# OMD_105V_5V_Buck.net
KiCad netlist of a schematic drawn in Altium Designer
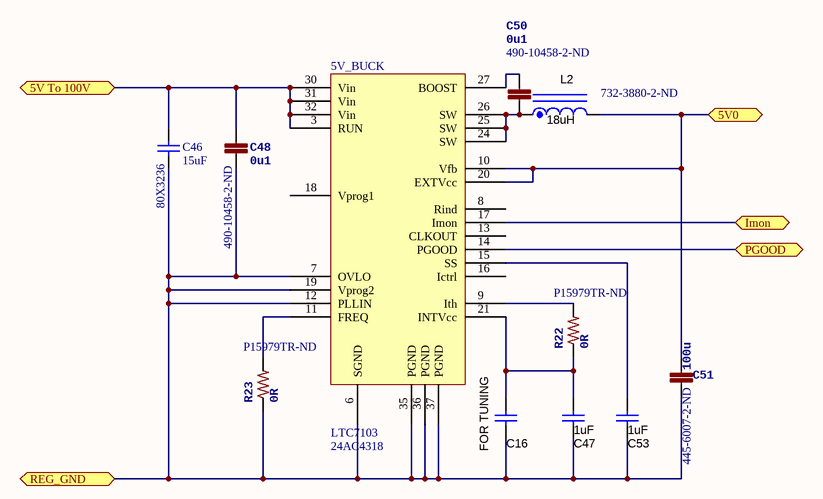
[diagram p0: OMD_105V_5V_Buck.SchDoc]

(export (version "E")
  (design (tool "Eeschema 10.0.6"))
  (components
    (comp (ref "5V_BUCK")
      (value "LTC7103")
      (footprint "LTC7103")
      (fields (field (name "SUPPLIER PART NUMBER 1") "24AC4318"))
      (libsource (lib "OMD") (part "LTC7103"))
    )
    (comp (ref "C16")
      (value "FOR TUNING")
      (footprint "0201-cap")
      (libsource (lib "OMD") (part "GRM188R70J105KA01D"))
    )
    (comp (ref "C46")
      (value "15uF")
      (footprint "CAPC5750L")
      (description "Capacitor")
      (fields (field (name "SUPPLIER PART NUMBER 1") "80X3236") (field (name "Comment") "Cap"))
      (libsource (lib "OMD") (part "Cap"))
    )
    (comp (ref "C47")
      (value "1uF")
      (footprint "0603-CAP")
      (description "CAP, CERM, 1 µF, 6.3 V, +/- 10%, X7R, 0603")
      (libsource (lib "OMD") (part "GRM188R70J105KA01D"))
    )
    (comp (ref "C48")
      (value "0u1")
      (footprint "0402-CAP")
      (description "CAP CER 0.1UF 16V Y5V 0402")
      (fields (field (name "SUPPLIER PART NUMBER 1") "490-10458-2-ND"))
      (libsource (lib "OMD") (part "CAP0402"))
    )
    (comp (ref "C50")
      (value "0u1")
      (footprint "0402-CAP")
      (description "CAP CER 0.1UF 16V Y5V 0402")
      (fields (field (name "SUPPLIER PART NUMBER 1") "490-10458-2-ND"))
      (libsource (lib "OMD") (part "CAP0402"))
    )
    (comp (ref "C51")
      (value "100u")
      (footprint "1206-CAP")
      (fields
        (field (name "PARTNO") "C3216X5R1A107M160AC")
        (field (name "SUPPLIER PART NUMBER 1") "445-6007-2-ND")
      )
      (libsource (lib "altium-import") (part "root_0_CAPACITOR-1206_"))
    )
    (comp (ref "C53")
      (value "1uF")
      (footprint "0603-CAP")
      (description "CAP, CERM, 1 µF, 6.3 V, +/- 10%, X7R, 0603")
      (libsource (lib "OMD") (part "GRM188R70J105KA01D"))
    )
    (comp (ref "L2")
      (value "18uH")
      (footprint "WE_IND")
      (description "Description FIXED IND 18UH 7.5A 22 MOHM SMD")
      (fields
        (field (name "SUPPLIER PART NUMBER 1") "732-3880-2-ND")
        (field (name "Comment") "732-3880-2-ND")
      )
      (libsource (lib "OMD") (part "SD53-150-R"))
    )
    (comp (ref "R22")
      (value "0R")
      (footprint "0201-RES")
      (description "RES 0OHM 1/16W 1% 0201 SMD")
      (fields (field (name "SUPPLIER PART NUMBER 1") "P15979TR-ND"))
      (libsource (lib "OMD") (part "RESISTOR0402-RES"))
    )
    (comp (ref "R23")
      (value "0R")
      (footprint "0201-RES")
      (description "RES 0OHM 1/16W 1% 0201 SMD")
      (fields (field (name "SUPPLIER PART NUMBER 1") "P15979TR-ND"))
      (libsource (lib "OMD") (part "RESISTOR0402-RES"))
    )
  )
  (nets
    (net (code "1") (name "/5V To 100V") (class "Default")
      (node (ref "5V_BUCK") (pin "3") (pinfunction "RUN_3") (pintype "passive"))
      (node (ref "5V_BUCK") (pin "30") (pinfunction "Vin_30") (pintype "passive"))
      (node (ref "5V_BUCK") (pin "31") (pinfunction "Vin_31") (pintype "passive"))
      (node (ref "5V_BUCK") (pin "32") (pinfunction "Vin_32") (pintype "passive"))
      (node (ref "C46") (pin "2") (pinfunction "2_2") (pintype "passive"))
      (node (ref "C48") (pin "P$1") (pinfunction "1_P$1") (pintype "passive"))
    )
    (net (code "2") (name "/5V0") (class "Default")
      (node (ref "5V_BUCK") (pin "10") (pinfunction "Vfb_10") (pintype "passive"))
      (node (ref "5V_BUCK") (pin "20") (pinfunction "EXTVcc_20") (pintype "passive"))
      (node (ref "C51") (pin "1") (pinfunction "1_1") (pintype "passive"))
      (node (ref "L2") (pin "2") (pinfunction "2_2") (pintype "passive"))
    )
    (net (code "3") (name "/Imon") (class "Default")
      (node (ref "5V_BUCK") (pin "17") (pinfunction "Imon_17") (pintype "passive"))
    )
    (net (code "4") (name "/PGOOD") (class "Default")
      (node (ref "5V_BUCK") (pin "14") (pinfunction "PGOOD_14") (pintype "passive"))
    )
    (net (code "5") (name "/REG_GND") (class "Default")
      (node (ref "5V_BUCK") (pin "12") (pinfunction "PLLIN_12") (pintype "passive"))
      (node (ref "5V_BUCK") (pin "19") (pinfunction "Vprog2_19") (pintype "passive"))
      (node (ref "5V_BUCK") (pin "35") (pinfunction "PGND_35") (pintype "passive"))
      (node (ref "5V_BUCK") (pin "36") (pinfunction "PGND_36") (pintype "passive"))
      (node (ref "5V_BUCK") (pin "37") (pinfunction "PGND_37") (pintype "passive"))
      (node (ref "5V_BUCK") (pin "6") (pinfunction "SGND_6") (pintype "passive"))
      (node (ref "5V_BUCK") (pin "7") (pinfunction "OVLO_7") (pintype "passive"))
      (node (ref "C16") (pin "1") (pinfunction "1_1") (pintype "passive"))
      (node (ref "C46") (pin "1") (pinfunction "1_1") (pintype "passive"))
      (node (ref "C47") (pin "1") (pinfunction "1_1") (pintype "passive"))
      (node (ref "C48") (pin "P$2") (pinfunction "2_P$2") (pintype "passive"))
      (node (ref "C51") (pin "2") (pinfunction "2_2") (pintype "passive"))
      (node (ref "C53") (pin "1") (pinfunction "1_1") (pintype "passive"))
      (node (ref "R23") (pin "1") (pinfunction "1_1") (pintype "passive"))
    )
    (net (code "6") (name "Net-(5V_BUCK-BOOST)") (class "Default")
      (node (ref "5V_BUCK") (pin "27") (pinfunction "BOOST_27") (pintype "passive"))
      (node (ref "C50") (pin "P$1") (pinfunction "1_P$1") (pintype "passive"))
    )
    (net (code "7") (name "Net-(5V_BUCK-FREQ)") (class "Default")
      (node (ref "5V_BUCK") (pin "11") (pinfunction "FREQ_11") (pintype "passive"))
      (node (ref "R23") (pin "2") (pinfunction "2_2") (pintype "passive"))
    )
    (net (code "8") (name "Net-(5V_BUCK-INTVcc)") (class "Default")
      (node (ref "5V_BUCK") (pin "21") (pinfunction "INTVcc_21") (pintype "passive"))
      (node (ref "C16") (pin "2") (pinfunction "2_2") (pintype "passive"))
      (node (ref "C47") (pin "2") (pinfunction "2_2") (pintype "passive"))
      (node (ref "R22") (pin "1") (pinfunction "1_1") (pintype "passive"))
    )
    (net (code "9") (name "Net-(5V_BUCK-Ith)") (class "Default")
      (node (ref "5V_BUCK") (pin "9") (pinfunction "Ith_9") (pintype "passive"))
      (node (ref "R22") (pin "2") (pinfunction "2_2") (pintype "passive"))
    )
    (net (code "10") (name "Net-(5V_BUCK-SS)") (class "Default")
      (node (ref "5V_BUCK") (pin "15") (pinfunction "SS_15") (pintype "passive"))
      (node (ref "C53") (pin "2") (pinfunction "2_2") (pintype "passive"))
    )
    (net (code "11") (name "Net-(C50-2)") (class "Default")
      (node (ref "5V_BUCK") (pin "24") (pinfunction "SW_24") (pintype "passive"))
      (node (ref "5V_BUCK") (pin "25") (pinfunction "SW_25") (pintype "passive"))
      (node (ref "5V_BUCK") (pin "26") (pinfunction "SW_26") (pintype "passive"))
      (node (ref "C50") (pin "P$2") (pinfunction "2_P$2") (pintype "passive"))
      (node (ref "L2") (pin "1") (pinfunction "1_1") (pintype "passive"))
    )
    (net (code "12") (name "unconnected-(5V_BUCK-CLKOUT-Pad13)") (class "Default")
      (node (ref "5V_BUCK") (pin "13") (pinfunction "CLKOUT_13") (pintype "passive"))
    )
    (net (code "13") (name "unconnected-(5V_BUCK-Ictrl-Pad16)") (class "Default")
      (node (ref "5V_BUCK") (pin "16") (pinfunction "Ictrl_16") (pintype "passive"))
    )
    (net (code "14") (name "unconnected-(5V_BUCK-Rind-Pad8)") (class "Default")
      (node (ref "5V_BUCK") (pin "8") (pinfunction "Rind_8") (pintype "passive"))
    )
    (net (code "15") (name "unconnected-(5V_BUCK-Vprog1-Pad18)") (class "Default")
      (node (ref "5V_BUCK") (pin "18") (pinfunction "Vprog1_18") (pintype "passive"))
    )
  )
)
